# Relay.net
KiCad netlist of a schematic drawn in Altium Designer
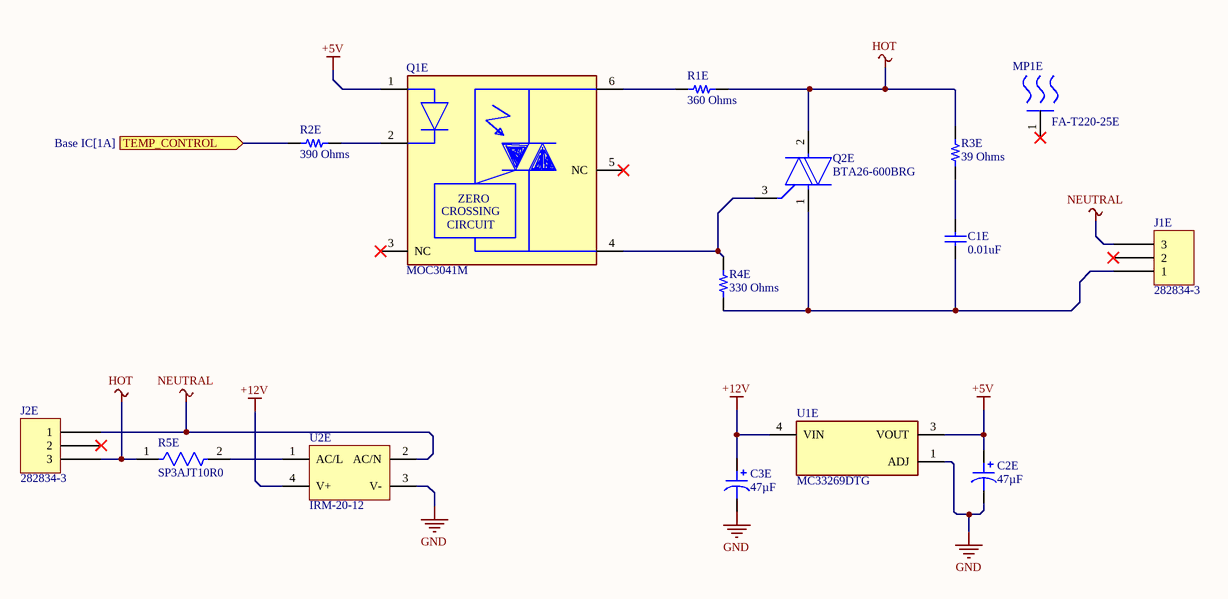
[diagram p0: Relay.SchDoc]

(export (version "E")
  (design (tool "Eeschema 10.0.6"))
  (components
    (comp (ref "C1E")
      (value "0.01uF")
      (footprint "WCAP-FTXX_L13W5H11_CS")
      (description "890334023006CS WCAP-FTXX Film Capacitor 10nF 310Vac")
      (fields (field (name "TOLERANCE") "10%"))
      (libsource (lib "Altium Content Vault") (part "Capacitor_Non-Polarized"))
    )
    (comp (ref "C2E")
      (value "47µF")
      (footprint "CAP ALSMD 6.6MM H5.4MM")
      (description "CAP ALUM 47UF 20% 16V SMD")
      (fields
        (field (name "PART NUMBER") "EEE-HA1C470P")
        (field (name "MANUFACTURER") "Panasonic Electronic Components")
      )
      (libsource (lib "Postgres Altium Library - altium_library") (part "Polarised Capacitor"))
    )
    (comp (ref "C3E")
      (value "47µF")
      (footprint "CAP ALSMD 6.6MM H5.4MM")
      (description "CAP ALUM 47UF 20% 16V SMD")
      (fields
        (field (name "PART NUMBER") "EEE-HA1C470P")
        (field (name "MANUFACTURER") "Panasonic Electronic Components")
      )
      (libsource (lib "Postgres Altium Library - altium_library") (part "Polarised Capacitor"))
    )
    (comp (ref "J1E")
      (value "282834-3")
      (footprint "TE 282834-3")
      (description "TERM BLK 3P SIDE ENT 2.54MM PCB")
      (fields (field (name "VOLTAGE") "150V") (field (name "MANUFACTURER") "TE Connectivity AMP Connectors"))
      (libsource (lib "") (part "3 Pin_1"))
    )
    (comp (ref "J2E")
      (value "282834-3")
      (footprint "TE 282834-3")
      (description "TERM BLK 3P SIDE ENT 2.54MM PCB")
      (fields (field (name "VOLTAGE") "150V") (field (name "MANUFACTURER") "TE Connectivity AMP Connectors"))
      (libsource (lib "Postgres Altium Library - altium_library") (part "3 Pin"))
    )
    (comp (ref "MP1E")
      (value "FA-T220-25E")
      (footprint "FP-FA-T220-25E-MFG")
      (description "HEATSINK TO-218,TO-220,TO-247")
      (libsource (lib "Altium Content Vault") (part "6f3fc7de95079af55ca25afa00d65c5"))
    )
    (comp (ref "Q1E")
      (value "MOC3041M")
      (footprint "FP-646BX-MFG")
      (description "OPTOISOLATOR 4.17KV TRIAC 6DIP")
      (fields
        (field (name "OCTOPART") "https://octopart.com/moc3041m-on+semiconductor-84330395")
        (field (name "MANUFACTURER") "ON Semiconductor")
      )
      (libsource (lib "Altium Content Vault") (part "55d433852054a47a4af1c6890e72339"))
    )
    (comp (ref "Q2E")
      (value "BTA26-600BRG")
      (footprint "FP-TOP3-MFG")
      (description "TRIAC 600V 25A TOP3")
      (fields
        (field (name "OCTOPART") "https://octopart.com/bta26-600brg-stmicroelectronics-132959")
        (field (name "MANUFACTURER") "STMicroelectronics")
      )
      (libsource (lib "Altium Content Vault") (part "f4fece21ac4a8209e2c36b39bc58009"))
    )
    (comp (ref "R1E")
      (value "360 Ohms")
      (footprint "RES 2512_6432")
      (description "RES 360 OHM 5% 1W 2512")
      (fields (field (name "PART NUMBER") "RK73B3ATTE361J") (field (name "TOLERANCE") "±5%"))
      (libsource (lib "Postgres Altium Library - altium_library") (part "Resistor"))
    )
    (comp (ref "R2E")
      (value "390 Ohms")
      (footprint "RES 0402_1005")
      (description "RES SMD 390 OHM 1% 1/16W 0402")
      (fields (field (name "PART NUMBER") "CR0402-FX-3900GLF") (field (name "TOLERANCE") "±1%"))
      (libsource (lib "Postgres Altium Library - altium_library") (part "Resistor"))
    )
    (comp (ref "R3E")
      (value "39 Ohms")
      (footprint "RES 2512_6432")
      (description "RES 39 OHM 5% 1W 2512")
      (fields (field (name "PART NUMBER") "RK73B3ATTE390J") (field (name "TOLERANCE") "±5%"))
      (libsource (lib "Postgres Altium Library - altium_library") (part "Resistor"))
    )
    (comp (ref "R4E")
      (value "330 Ohms")
      (footprint "RES 2512_6432")
      (description "RES 330 OHM 1% 1W 2512")
      (fields (field (name "PART NUMBER") "RK73H3ATTE3300F") (field (name "TOLERANCE") "±1%"))
      (libsource (lib "Postgres Altium Library - altium_library") (part "Resistor"))
    )
    (comp (ref "R5E")
      (value "SP3AJT10R0")
      (footprint "FP-SP3A-MFG")
      (description "RES 10 OHM 5% 4W AXIAL")
      (fields (field (name "TOLERANCE") "5%"))
      (libsource (lib "Altium Content Vault") (part "1029c3af85768c4190bb7ad29bc67b5"))
    )
    (comp (ref "U1E")
      (value "MC33269DTG")
      (footprint "FP-369C-MFG")
      (libsource (lib "Altium Content Vault") (part "301fc8db1ac6b3fd6cc8ef0b07c4af6"))
    )
    (comp (ref "U2E")
      (value "IRM-20-12")
      (footprint "MEANW-IRM-20-12")
      (description "Single Output Encapsulated Type, 12 V, 1.8 A, 21.6 W, -40 to 85 degC, 4-Pin THD, RoHS")
      (fields (field (name "MANUFACTURER") "Mean Well"))
      (libsource (lib "Altium Content Vault") (part "MEANW-IRM-20-12-4"))
    )
  )
  (nets
    (net (code "1") (name "+5V") (class "Default")
      (node (ref "C2E") (pin "1") (pinfunction "1_1") (pintype "passive"))
      (node (ref "Q1E") (pin "1") (pinfunction "A_1") (pintype "passive"))
      (node (ref "U1E") (pin "3") (pinfunction "VOUT_3") (pintype "passive"))
    )
    (net (code "2") (name "+12V") (class "Default")
      (node (ref "C3E") (pin "1") (pinfunction "1_1") (pintype "passive"))
      (node (ref "U1E") (pin "4") (pinfunction "VIN_4") (pintype "power_in"))
      (node (ref "U2E") (pin "4") (pinfunction "V+_4") (pintype "power_in"))
    )
    (net (code "3") (name "/TEMP_CONTROL") (class "Default")
      (node (ref "R2E") (pin "1") (pinfunction "1_1") (pintype "passive"))
    )
    (net (code "4") (name "GND") (class "Default")
      (node (ref "C2E") (pin "2") (pinfunction "2_2") (pintype "passive"))
      (node (ref "C3E") (pin "2") (pinfunction "2_2") (pintype "passive"))
      (node (ref "U1E") (pin "1") (pinfunction "ADJ_1") (pintype "passive"))
      (node (ref "U2E") (pin "3") (pinfunction "V-_3") (pintype "power_in"))
    )
    (net (code "5") (name "HOT") (class "Default")
      (node (ref "J2E") (pin "3") (pinfunction "3_3") (pintype "passive"))
      (node (ref "Q2E") (pin "2") (pinfunction "A2_2") (pintype "passive"))
      (node (ref "R1E") (pin "2") (pinfunction "2_2") (pintype "passive"))
      (node (ref "R3E") (pin "2") (pinfunction "2_2") (pintype "passive"))
      (node (ref "R5E") (pin "1") (pinfunction "1_1") (pintype "passive"))
    )
    (net (code "6") (name "NEUTRAL") (class "Default")
      (node (ref "J1E") (pin "3") (pinfunction "3_3") (pintype "passive"))
      (node (ref "J2E") (pin "1") (pinfunction "1_1") (pintype "passive"))
      (node (ref "U2E") (pin "2") (pinfunction "AC/N_2") (pintype "passive"))
    )
    (net (code "7") (name "Net-(C1E-Pad2)") (class "Default")
      (node (ref "C1E") (pin "2") (pinfunction "2_2") (pintype "passive"))
      (node (ref "R3E") (pin "1") (pinfunction "1_1") (pintype "passive"))
    )
    (net (code "8") (name "Net-(Q1E-1_MAIN_TERM.)") (class "Default")
      (node (ref "Q1E") (pin "4") (pinfunction "1_MAIN_TERM._4") (pintype "passive"))
      (node (ref "Q2E") (pin "3") (pinfunction "G_3") (pintype "passive"))
      (node (ref "R4E") (pin "2") (pinfunction "2_2") (pintype "passive"))
    )
    (net (code "9") (name "Net-(Q1E-2_MAIN_TERM.)") (class "Default")
      (node (ref "Q1E") (pin "6") (pinfunction "2_MAIN_TERM._6") (pintype "passive"))
      (node (ref "R1E") (pin "1") (pinfunction "1_1") (pintype "passive"))
    )
    (net (code "10") (name "Net-(Q1E-C)") (class "Default")
      (node (ref "Q1E") (pin "2") (pinfunction "C_2") (pintype "passive"))
      (node (ref "R2E") (pin "2") (pinfunction "2_2") (pintype "passive"))
    )
    (net (code "11") (name "Net-(Q2E-A1)") (class "Default")
      (node (ref "C1E") (pin "1") (pinfunction "1_1") (pintype "passive"))
      (node (ref "J1E") (pin "1") (pinfunction "1_1") (pintype "passive"))
      (node (ref "Q2E") (pin "1") (pinfunction "A1_1") (pintype "passive"))
      (node (ref "R4E") (pin "1") (pinfunction "1_1") (pintype "passive"))
    )
    (net (code "12") (name "Net-(U2E-AC{slash}L)") (class "Default")
      (node (ref "R5E") (pin "2") (pinfunction "2_2") (pintype "passive"))
      (node (ref "U2E") (pin "1") (pinfunction "AC/L_1") (pintype "passive"))
    )
    (net (code "13") (name "unconnected-(J1E-Pad2)") (class "Default")
      (node (ref "J1E") (pin "2") (pinfunction "2_2") (pintype "passive+no_connect"))
    )
    (net (code "14") (name "unconnected-(J2E-Pad2)") (class "Default")
      (node (ref "J2E") (pin "2") (pinfunction "2_2") (pintype "passive+no_connect"))
    )
    (net (code "15") (name "unconnected-(MP1E-MNT_1-Pad1)") (class "Default")
      (node (ref "MP1E") (pin "1") (pinfunction "MNT_1_1") (pintype "passive+no_connect"))
    )
    (net (code "16") (name "unconnected-(Q1E-NC-Pad3)") (class "Default")
      (node (ref "Q1E") (pin "3") (pinfunction "NC_3") (pintype "passive+no_connect"))
    )
    (net (code "17") (name "unconnected-(Q1E-NC-Pad5)") (class "Default")
      (node (ref "Q1E") (pin "5") (pinfunction "NC_5") (pintype "passive+no_connect"))
    )
  )
)
